# Sync_Decoder.net
KiCad netlist of a schematic drawn in Altium Designer
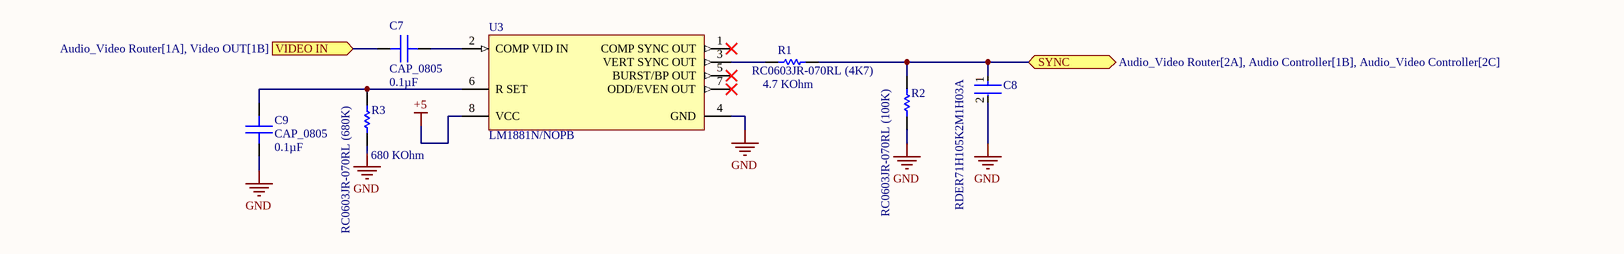
[diagram p0: Sync Decoder.SchDoc]

(export (version "E")
  (design (tool "Eeschema 10.0.6"))
  (components
    (comp (ref "C7")
      (value "CAP_0805")
      (footprint "0805_CAPACITOR_DCACERES")
      (description "Capacitor SMD, encapsulado 0805")
      (fields (field (name "ALTIUM_VALUE") "0.1µF"))
      (libsource (lib "PF_Schlib") (part "CAPACITOR_0805_Caceres"))
    )
    (comp (ref "C8")
      (value "RDER71H105K2M1H03A")
      (footprint "FP-RDE2M1-MFG")
      (description "Ceramic Capacitor 1uF ±10% 50V X7R Radial")
      (fields (field (name "TOLERANCE") "10%"))
      (libsource (lib "Altium Content Vault") (part "b4654b650e69147ec39a6b967a45e02"))
    )
    (comp (ref "C9")
      (value "CAP_0805")
      (footprint "0805_CAPACITOR_DCACERES")
      (description "Capacitor SMD, encapsulado 0805")
      (fields (field (name "ALTIUM_VALUE") "0.1µF"))
      (libsource (lib "PF_Schlib") (part "CAPACITOR_0805_Caceres"))
    )
    (comp (ref "R1")
      (value "RC0603JR-070RL (4K7)")
      (footprint "RESC1608X55X25ML10T15")
      (description "Chip Resistor, 0 Ohm, +/- 5%, 0.1 W, -55 to 155 degC, 0603 (1608 Metric), RoHS, Tape and Reel")
      (fields
        (field (name "TOLERANCE") "5%")
        (field (name "RESISTANCE") "4.7 KOhm")
        (field (name "MANUFACTURER") "Yageo")
      )
      (libsource (lib "Altium Content Vault") (part "RES-2"))
    )
    (comp (ref "R2")
      (value "RC0603JR-070RL (100K)")
      (footprint "RESC1608X55X25ML10T15")
      (description "Chip Resistor, 0 Ohm, +/- 5%, 0.1 W, -55 to 155 degC, 0603 (1608 Metric), RoHS, Tape and Reel")
      (fields (field (name "TOLERANCE") "5%") (field (name "MANUFACTURER") "Yageo"))
      (libsource (lib "Altium Content Vault") (part "RES-2"))
    )
    (comp (ref "R3")
      (value "RC0603JR-070RL (680K)")
      (footprint "RESC1608X55X25ML10T15")
      (description "Chip Resistor, 0 Ohm, +/- 5%, 0.1 W, -55 to 155 degC, 0603 (1608 Metric), RoHS, Tape and Reel")
      (fields
        (field (name "TOLERANCE") "5%")
        (field (name "RESISTANCE") "680 KOhm")
        (field (name "MANUFACTURER") "Yageo")
      )
      (libsource (lib "Altium Content Vault") (part "RES-2"))
    )
    (comp (ref "U3")
      (value "LM1881N/NOPB")
      (footprint "P0008A")
      (description "Video Sync Separator, 8-pin MDIP, Pb-Free")
      (fields (field (name "MANUFACTURER") "Texas Instruments"))
      (libsource (lib "Altium Content Vault") (part "VID-SYNC-LM1881-8"))
    )
  )
  (nets
    (net (code "1") (name "+5") (class "Default")
      (node (ref "U3") (pin "8") (pinfunction "VCC_8") (pintype "power_in"))
    )
    (net (code "2") (name "/SYNC") (class "Default")
      (node (ref "C8") (pin "1") (pinfunction "1_1") (pintype "passive"))
      (node (ref "R1") (pin "1") (pinfunction "1_1") (pintype "passive"))
      (node (ref "R2") (pin "2") (pinfunction "2_2") (pintype "passive"))
    )
    (net (code "3") (name "/VIDEO IN") (class "Default")
      (node (ref "C7") (pin "1") (pinfunction "1_1") (pintype "passive"))
    )
    (net (code "4") (name "GND") (class "Default")
      (node (ref "C8") (pin "2") (pinfunction "2_2") (pintype "passive"))
      (node (ref "C9") (pin "1") (pinfunction "1_1") (pintype "passive"))
      (node (ref "R2") (pin "1") (pinfunction "1_1") (pintype "passive"))
      (node (ref "R3") (pin "1") (pinfunction "1_1") (pintype "passive"))
      (node (ref "U3") (pin "4") (pinfunction "GND_4") (pintype "power_in"))
    )
    (net (code "5") (name "Net-(U3-COMP_VID_IN)") (class "Default")
      (node (ref "C7") (pin "2") (pinfunction "2_2") (pintype "passive"))
      (node (ref "U3") (pin "2") (pinfunction "COMP_VID_IN_2") (pintype "input"))
    )
    (net (code "6") (name "Net-(U3-R_SET)") (class "Default")
      (node (ref "C9") (pin "2") (pinfunction "2_2") (pintype "passive"))
      (node (ref "R3") (pin "2") (pinfunction "2_2") (pintype "passive"))
      (node (ref "U3") (pin "6") (pinfunction "R_SET_6") (pintype "passive"))
    )
    (net (code "7") (name "Net-(U3-VERT_SYNC_OUT)") (class "Default")
      (node (ref "R1") (pin "2") (pinfunction "2_2") (pintype "passive"))
      (node (ref "U3") (pin "3") (pinfunction "VERT_SYNC_OUT_3") (pintype "output"))
    )
    (net (code "8") (name "unconnected-(U3-BURST{slash}BP_OUT-Pad5)") (class "Default")
      (node (ref "U3") (pin "5") (pinfunction "BURST/BP_OUT_5") (pintype "output+no_connect"))
    )
    (net (code "9") (name "unconnected-(U3-COMP_SYNC_OUT-Pad1)") (class "Default")
      (node (ref "U3") (pin "1") (pinfunction "COMP_SYNC_OUT_1") (pintype "output+no_connect"))
    )
    (net (code "10") (name "unconnected-(U3-ODD{slash}EVEN_OUT-Pad7)") (class "Default")
      (node (ref "U3") (pin "7") (pinfunction "ODD/EVEN_OUT_7") (pintype "output+no_connect"))
    )
  )
)
